# Minimum_LPC2148_2.net
KiCad netlist of a schematic drawn in EAGLE
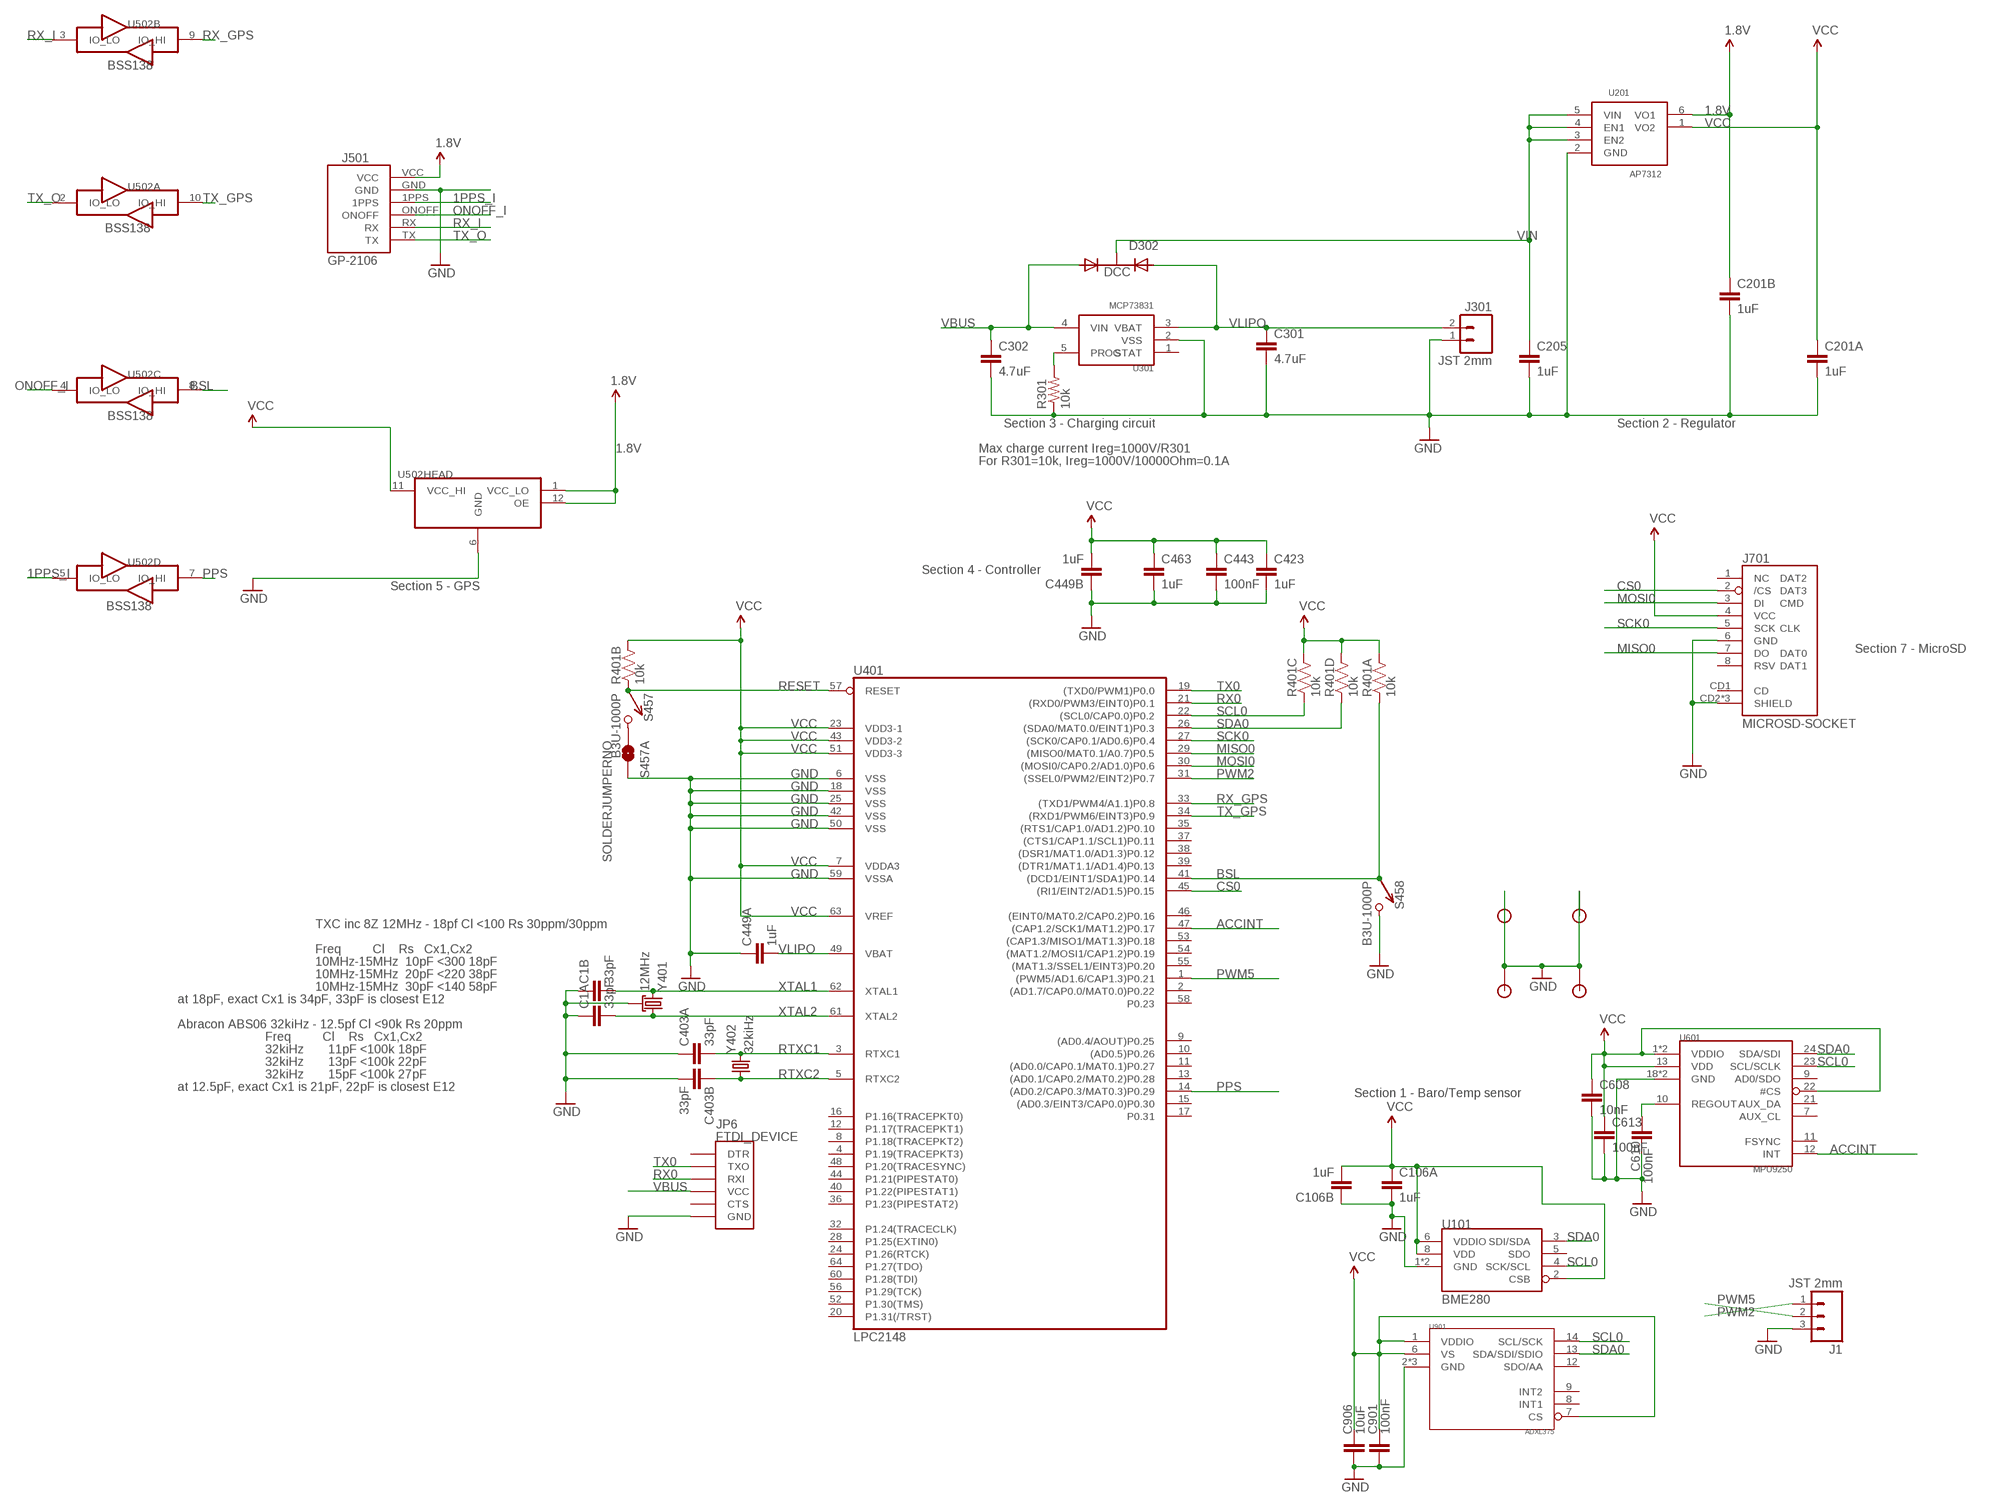
[diagram p0: schematic, sheet 1]

(export (version "E")
  (design (tool "Eeschema 10.0.6"))
  (components
    (comp (ref "C1")
      (value "33pF")
      (footprint "eagle-import:CKCM25")
      (libsource (lib "eagle-import") (part "CKCM25"))
    )
    (comp (ref "C106")
      (value "1uF")
      (footprint "eagle-import:CKCM25")
      (libsource (lib "eagle-import") (part "CKCM25"))
    )
    (comp (ref "C201")
      (value "1uF")
      (footprint "eagle-import:CKCM25")
      (libsource (lib "eagle-import") (part "CKCM25"))
    )
    (comp (ref "C205")
      (value "1uF")
      (footprint "eagle-import:0402-CAP")
      (libsource (lib "eagle-import") (part "CAP0402-CAP"))
    )
    (comp (ref "C301")
      (value "4.7uF")
      (footprint "eagle-import:0402-CAP")
      (libsource (lib "eagle-import") (part "CAP0402-CAP"))
    )
    (comp (ref "C302")
      (value "4.7uF")
      (footprint "eagle-import:0402-CAP")
      (libsource (lib "eagle-import") (part "CAP0402-CAP"))
    )
    (comp (ref "C403")
      (value "33pF")
      (footprint "eagle-import:CKCM25")
      (libsource (lib "eagle-import") (part "CKCM25"))
    )
    (comp (ref "C423")
      (value "1uF")
      (footprint "eagle-import:0402-CAP")
      (libsource (lib "eagle-import") (part "CAP0402-CAP"))
    )
    (comp (ref "C443")
      (value "100nF")
      (footprint "eagle-import:0402-CAP")
      (libsource (lib "eagle-import") (part "CAP0402-CAP"))
    )
    (comp (ref "C449")
      (value "1uF")
      (footprint "eagle-import:CKCM25")
      (libsource (lib "eagle-import") (part "CKCM25"))
    )
    (comp (ref "C463")
      (value "1uF")
      (footprint "eagle-import:0402-CAP")
      (libsource (lib "eagle-import") (part "CAP0402-CAP"))
    )
    (comp (ref "C608")
      (value "10nF")
      (footprint "eagle-import:0402-CAP")
      (libsource (lib "eagle-import") (part "CAP0402-CAP"))
    )
    (comp (ref "C610")
      (value "100nF")
      (footprint "eagle-import:0402-CAP")
      (libsource (lib "eagle-import") (part "CAP0402-CAP"))
    )
    (comp (ref "C613")
      (value "100nF")
      (footprint "eagle-import:0402-CAP")
      (libsource (lib "eagle-import") (part "CAP0402-CAP"))
    )
    (comp (ref "C901")
      (value "100nF")
      (footprint "eagle-import:0402-CAP")
      (libsource (lib "eagle-import") (part "SparkFun-Passives_CAP0402-CAP"))
    )
    (comp (ref "C906")
      (value "10uF")
      (footprint "eagle-import:0603-CAP")
      (libsource (lib "eagle-import") (part "CAP0603-CAP"))
    )
    (comp (ref "D302")
      (value "DCC")
      (footprint "eagle-import:SOT-23-3")
      (libsource (lib "eagle-import") (part "PMEG2005CT"))
    )
    (comp (ref "J1")
      (value "JST 2mm")
      (footprint "eagle-import:1X03_NO_SILK")
      (libsource (lib "eagle-import") (part "M031X03_NO_SILK"))
    )
    (comp (ref "J301")
      (value "JST 2mm")
      (footprint "eagle-import:1X02_NO_SILK")
      (libsource (lib "eagle-import") (part "M021X02_NO_SILK"))
    )
    (comp (ref "J501")
      (value "GP-2106")
      (footprint "eagle-import:GP-2106")
      (libsource (lib "eagle-import") (part "GP-2106"))
    )
    (comp (ref "J701")
      (value "MICROSD-SOCKET")
      (footprint "eagle-import:MICROSD-SOCKET-PP")
      (libsource (lib "eagle-import") (part "MICROSD-SOCKET"))
    )
    (comp (ref "JP1")
      (value "STANDOFF")
      (footprint "eagle-import:STANDOFF")
      (libsource (lib "eagle-import") (part "STANDOFF"))
    )
    (comp (ref "JP2")
      (value "STANDOFF")
      (footprint "eagle-import:STANDOFF")
      (libsource (lib "eagle-import") (part "STANDOFF"))
    )
    (comp (ref "JP4")
      (value "STANDOFF")
      (footprint "eagle-import:STANDOFF")
      (libsource (lib "eagle-import") (part "STANDOFF"))
    )
    (comp (ref "JP5")
      (value "STANDOFF")
      (footprint "eagle-import:STANDOFF")
      (libsource (lib "eagle-import") (part "STANDOFF"))
    )
    (comp (ref "JP6")
      (value "FTDI_DEVICE")
      (footprint "eagle-import:FTDI_DEVICE_SIDE")
      (libsource (lib "eagle-import") (part "FTDI_DEVICE"))
    )
    (comp (ref "R301")
      (value "10k")
      (footprint "eagle-import:0402-RES")
      (libsource (lib "eagle-import") (part "RESISTOR0402-RES"))
    )
    (comp (ref "R401")
      (value "10k")
      (footprint "eagle-import:CRA04")
      (fields (field (name "DIGIKEY") "CRA4S810KCT-ND"))
      (libsource (lib "eagle-import") (part "RP404"))
    )
    (comp (ref "S457")
      (value "B3U-1000P")
      (footprint "eagle-import:B3U-1000P")
      (libsource (lib "eagle-import") (part "B3U-1000P"))
    )
    (comp (ref "S457A")
      (value "SOLDERJUMPERNO")
      (footprint "eagle-import:SJ_2S-NO")
      (libsource (lib "eagle-import") (part "SOLDERJUMPERNO"))
    )
    (comp (ref "S458")
      (value "B3U-1000P")
      (footprint "eagle-import:B3U-1000P")
      (libsource (lib "eagle-import") (part "B3U-1000P"))
    )
    (comp (ref "U101")
      (value "BME280")
      (footprint "eagle-import:BME280")
      (libsource (lib "eagle-import") (part "BME280"))
    )
    (comp (ref "U201")
      (value "AP7312")
      (footprint "eagle-import:SOT-23-6")
      (libsource (lib "eagle-import") (part "AP73X2"))
    )
    (comp (ref "U301")
      (value "MCP73831")
      (footprint "eagle-import:SOT-23-5")
      (libsource (lib "eagle-import") (part "MCP73831"))
    )
    (comp (ref "U401")
      (value "LPC2148")
      (footprint "eagle-import:SQFP-S-10X10-64")
      (libsource (lib "eagle-import") (part "LPC213X"))
    )
    (comp (ref "U502")
      (value "TXB0104RUT")
      (footprint "eagle-import:R-PUQFN-N12")
      (libsource (lib "eagle-import") (part "TXB0104RUT"))
    )
    (comp (ref "U601")
      (value "MPU9250")
      (footprint "eagle-import:LQFN_3MM_3MM")
      (libsource (lib "eagle-import") (part "MPU9250"))
    )
    (comp (ref "U901")
      (value "ADXL375")
      (footprint "eagle-import:ADXL375")
      (libsource (lib "eagle-import") (part "ADXL375"))
    )
    (comp (ref "Y401")
      (value "12MHz")
      (footprint "eagle-import:CRYSTAL_SMD_2MM_2_5MM")
      (libsource (lib "eagle-import") (part "CX2520"))
    )
    (comp (ref "Y402")
      (value "32kiHz")
      (footprint "eagle-import:ABS06")
      (libsource (lib "eagle-import") (part "ABS06"))
    )
  )
  (nets
    (net (code "1") (name "/1PPS_I") (class "Default")
      (node (ref "J501") (pin "1PPS") (pinfunction "1PPS_1PPS") (pintype "bidirectional"))
      (node (ref "U502") (pin "5") (pinfunction "IO_LO_5") (pintype "bidirectional"))
    )
    (net (code "2") (name "/ACCINT") (class "Default")
      (node (ref "U401") (pin "47") (pinfunction "(CAP1.2/SCK1/MAT1.2)P0.17_47") (pintype "bidirectional"))
      (node (ref "U601") (pin "12") (pinfunction "INT_12") (pintype "bidirectional"))
    )
    (net (code "3") (name "/BSL") (class "Default")
      (node (ref "R401") (pin "1") (pinfunction "1_1") (pintype "passive"))
      (node (ref "S458") (pin "P$1") (pinfunction "1_P$1") (pintype "bidirectional"))
      (node (ref "U401") (pin "41") (pinfunction "(DCD1/EINT1/SDA1)P0.14_41") (pintype "bidirectional"))
      (node (ref "U502") (pin "8") (pinfunction "IO_HI_8") (pintype "bidirectional"))
    )
    (net (code "4") (name "/CS0") (class "Default")
      (node (ref "J701") (pin "2") (pinfunction "/CS_2") (pintype "bidirectional"))
      (node (ref "U401") (pin "45") (pinfunction "(RI1/EINT2/AD1.5)P0.15_45") (pintype "bidirectional"))
    )
    (net (code "5") (name "/MISO0") (class "Default")
      (node (ref "J701") (pin "7") (pinfunction "DO_7") (pintype "bidirectional"))
      (node (ref "U401") (pin "29") (pinfunction "(MISO0/MAT0.1/A0.7)P0.5_29") (pintype "bidirectional"))
    )
    (net (code "6") (name "/MOSI0") (class "Default")
      (node (ref "J701") (pin "3") (pinfunction "DI_3") (pintype "bidirectional"))
      (node (ref "U401") (pin "30") (pinfunction "(MOSI0/CAP0.2/AD1.0)P0.6_30") (pintype "bidirectional"))
    )
    (net (code "7") (name "/ONOFF_I") (class "Default")
      (node (ref "J501") (pin "ONOFF") (pinfunction "ONOFF_ONOFF") (pintype "bidirectional"))
      (node (ref "U502") (pin "4") (pinfunction "IO_LO_4") (pintype "bidirectional"))
    )
    (net (code "8") (name "/PPS") (class "Default")
      (node (ref "U401") (pin "14") (pinfunction "(AD0.2/CAP0.3/MAT0.3)P0.29_14") (pintype "bidirectional"))
      (node (ref "U502") (pin "7") (pinfunction "IO_HI_7") (pintype "bidirectional"))
    )
    (net (code "9") (name "/PWM2") (class "Default")
      (node (ref "J1") (pin "1") (pinfunction "1_1") (pintype "passive"))
      (node (ref "U401") (pin "31") (pinfunction "(SSEL0/PWM2/EINT2)P0.7_31") (pintype "bidirectional"))
    )
    (net (code "10") (name "/PWM5") (class "Default")
      (node (ref "J1") (pin "2") (pinfunction "2_2") (pintype "passive"))
      (node (ref "U401") (pin "1") (pinfunction "(PWM5/AD1.6/CAP1.3)P0.21_1") (pintype "bidirectional"))
    )
    (net (code "11") (name "/RESET") (class "Default")
      (node (ref "R401") (pin "2") (pinfunction "1_2") (pintype "passive"))
      (node (ref "S457") (pin "P$1") (pinfunction "1_P$1") (pintype "bidirectional"))
      (node (ref "U401") (pin "57") (pinfunction "RESET_57") (pintype "input"))
    )
    (net (code "12") (name "/RTXC1") (class "Default")
      (node (ref "C403") (pin "4") (pinfunction "2_4") (pintype "passive"))
      (node (ref "U401") (pin "3") (pinfunction "RTXC1_3") (pintype "input"))
      (node (ref "Y402") (pin "2") (pinfunction "2_2") (pintype "passive"))
    )
    (net (code "13") (name "/RTXC2") (class "Default")
      (node (ref "C403") (pin "2") (pinfunction "1_2") (pintype "passive"))
      (node (ref "U401") (pin "5") (pinfunction "RTXC2_5") (pintype "output"))
      (node (ref "Y402") (pin "1") (pinfunction "1_1") (pintype "passive"))
    )
    (net (code "14") (name "/RX0") (class "Default")
      (node (ref "JP6") (pin "P$3") (pinfunction "RXI_P$3") (pintype "bidirectional"))
      (node (ref "U401") (pin "21") (pinfunction "(RXD0/PWM3/EINT0)P0.1_21") (pintype "bidirectional"))
    )
    (net (code "15") (name "/RX_GPS") (class "Default")
      (node (ref "U401") (pin "33") (pinfunction "(TXD1/PWM4/A1.1)P0.8_33") (pintype "bidirectional"))
      (node (ref "U502") (pin "9") (pinfunction "IO_HI_9") (pintype "bidirectional"))
    )
    (net (code "16") (name "/RX_I") (class "Default")
      (node (ref "J501") (pin "RX") (pinfunction "RX_RX") (pintype "bidirectional"))
      (node (ref "U502") (pin "3") (pinfunction "IO_LO_3") (pintype "bidirectional"))
    )
    (net (code "17") (name "/SCK0") (class "Default")
      (node (ref "J701") (pin "5") (pinfunction "SCK_5") (pintype "bidirectional"))
      (node (ref "U401") (pin "27") (pinfunction "(SCK0/CAP0.1/AD0.6)P0.4_27") (pintype "bidirectional"))
    )
    (net (code "18") (name "/SCL0") (class "Default")
      (node (ref "R401") (pin "3") (pinfunction "1_3") (pintype "passive"))
      (node (ref "U101") (pin "4") (pinfunction "SCK/SCL_4") (pintype "input"))
      (node (ref "U401") (pin "22") (pinfunction "(SCL0/CAP0.0)P0.2_22") (pintype "bidirectional"))
      (node (ref "U601") (pin "23") (pinfunction "SCL/SCLK_23") (pintype "bidirectional"))
      (node (ref "U901") (pin "14") (pinfunction "SCL/SCK_14") (pintype "input"))
    )
    (net (code "19") (name "/SDA0") (class "Default")
      (node (ref "R401") (pin "4") (pinfunction "1_4") (pintype "passive"))
      (node (ref "U101") (pin "3") (pinfunction "SDI/SDA_3") (pintype "bidirectional"))
      (node (ref "U401") (pin "26") (pinfunction "(SDA0/MAT0.0/EINT1)P0.3_26") (pintype "bidirectional"))
      (node (ref "U601") (pin "24") (pinfunction "SDA/SDI_24") (pintype "bidirectional"))
      (node (ref "U901") (pin "13") (pinfunction "SDA/SDI/SDIO_13") (pintype "bidirectional"))
    )
    (net (code "20") (name "/TX0") (class "Default")
      (node (ref "JP6") (pin "P$2") (pinfunction "TXO_P$2") (pintype "bidirectional"))
      (node (ref "U401") (pin "19") (pinfunction "(TXD0/PWM1)P0.0_19") (pintype "bidirectional"))
    )
    (net (code "21") (name "/TX_GPS") (class "Default")
      (node (ref "U401") (pin "34") (pinfunction "(RXD1/PWM6/EINT3)P0.9_34") (pintype "bidirectional"))
      (node (ref "U502") (pin "10") (pinfunction "IO_HI_10") (pintype "bidirectional"))
    )
    (net (code "22") (name "/TX_O") (class "Default")
      (node (ref "J501") (pin "TX") (pinfunction "TX_TX") (pintype "bidirectional"))
      (node (ref "U502") (pin "2") (pinfunction "IO_LO_2") (pintype "bidirectional"))
    )
    (net (code "23") (name "/VBUS") (class "Default")
      (node (ref "C302") (pin "1") (pinfunction "1_1") (pintype "passive"))
      (node (ref "D302") (pin "1") (pinfunction "A1_1") (pintype "passive"))
      (node (ref "JP6") (pin "P$4") (pinfunction "VCC_P$4") (pintype "bidirectional"))
      (node (ref "U301") (pin "4") (pinfunction "VIN_4") (pintype "power_in"))
    )
    (net (code "24") (name "/VIN") (class "Default")
      (node (ref "C205") (pin "1") (pinfunction "1_1") (pintype "passive"))
      (node (ref "D302") (pin "3") (pinfunction "K_3") (pintype "passive"))
      (node (ref "U201") (pin "3") (pinfunction "EN2_3") (pintype "bidirectional"))
      (node (ref "U201") (pin "4") (pinfunction "EN1_4") (pintype "bidirectional"))
      (node (ref "U201") (pin "5") (pinfunction "VIN_5") (pintype "bidirectional"))
    )
    (net (code "25") (name "/VLIPO") (class "Default")
      (node (ref "C301") (pin "1") (pinfunction "1_1") (pintype "passive"))
      (node (ref "C449") (pin "4") (pinfunction "2_4") (pintype "passive"))
      (node (ref "D302") (pin "2") (pinfunction "A2_2") (pintype "passive"))
      (node (ref "J301") (pin "2") (pinfunction "2_2") (pintype "passive"))
      (node (ref "U301") (pin "3") (pinfunction "VBAT_3") (pintype "power_in"))
      (node (ref "U401") (pin "49") (pinfunction "VBAT_49") (pintype "power_in"))
    )
    (net (code "26") (name "/XTAL1") (class "Default")
      (node (ref "C1") (pin "3") (pinfunction "2_3") (pintype "passive"))
      (node (ref "U401") (pin "62") (pinfunction "XTAL1_62") (pintype "input"))
      (node (ref "Y401") (pin "3") (pinfunction "2_3") (pintype "passive"))
    )
    (net (code "27") (name "/XTAL2") (class "Default")
      (node (ref "C1") (pin "4") (pinfunction "2_4") (pintype "passive"))
      (node (ref "U401") (pin "61") (pinfunction "XTAL2_61") (pintype "output"))
      (node (ref "Y401") (pin "1") (pinfunction "1_1") (pintype "passive"))
    )
    (net (code "28") (name "1.8V") (class "Default")
      (node (ref "C201") (pin "2") (pinfunction "1_2") (pintype "passive"))
      (node (ref "J501") (pin "VCC") (pinfunction "VCC_VCC") (pintype "bidirectional"))
      (node (ref "U201") (pin "6") (pinfunction "VO1_6") (pintype "bidirectional"))
      (node (ref "U502") (pin "1") (pinfunction "VCC_LO_1") (pintype "power_in"))
      (node (ref "U502") (pin "12") (pinfunction "OE_12") (pintype "bidirectional"))
    )
    (net (code "29") (name "GND") (class "Default")
      (node (ref "C1") (pin "1") (pinfunction "1_1") (pintype "passive"))
      (node (ref "C1") (pin "2") (pinfunction "1_2") (pintype "passive"))
      (node (ref "C106") (pin "2") (pinfunction "1_2") (pintype "passive"))
      (node (ref "C106") (pin "4") (pinfunction "2_4") (pintype "passive"))
      (node (ref "C201") (pin "3") (pinfunction "2_3") (pintype "passive"))
      (node (ref "C201") (pin "4") (pinfunction "2_4") (pintype "passive"))
      (node (ref "C205") (pin "2") (pinfunction "2_2") (pintype "passive"))
      (node (ref "C301") (pin "2") (pinfunction "2_2") (pintype "passive"))
      (node (ref "C302") (pin "2") (pinfunction "2_2") (pintype "passive"))
      (node (ref "C403") (pin "1") (pinfunction "1_1") (pintype "passive"))
      (node (ref "C403") (pin "3") (pinfunction "2_3") (pintype "passive"))
      (node (ref "C423") (pin "2") (pinfunction "2_2") (pintype "passive"))
      (node (ref "C443") (pin "2") (pinfunction "2_2") (pintype "passive"))
      (node (ref "C449") (pin "1") (pinfunction "1_1") (pintype "passive"))
      (node (ref "C449") (pin "2") (pinfunction "1_2") (pintype "passive"))
      (node (ref "C463") (pin "2") (pinfunction "2_2") (pintype "passive"))
      (node (ref "C608") (pin "2") (pinfunction "2_2") (pintype "passive"))
      (node (ref "C610") (pin "2") (pinfunction "2_2") (pintype "passive"))
      (node (ref "C613") (pin "2") (pinfunction "2_2") (pintype "passive"))
      (node (ref "C901") (pin "2") (pinfunction "2_2") (pintype "passive"))
      (node (ref "C906") (pin "2") (pinfunction "2_2") (pintype "passive"))
      (node (ref "J1") (pin "3") (pinfunction "3_3") (pintype "passive"))
      (node (ref "J301") (pin "1") (pinfunction "1_1") (pintype "passive"))
      (node (ref "J501") (pin "GND") (pinfunction "GND_GND") (pintype "bidirectional"))
      (node (ref "J701") (pin "6") (pinfunction "GND_6") (pintype "bidirectional"))
      (node (ref "J701") (pin "CD2") (pinfunction "SHIELD_CD2") (pintype "bidirectional"))
      (node (ref "J701") (pin "GND1") (pinfunction "SHIELD_GND1") (pintype "bidirectional"))
      (node (ref "J701") (pin "GND3") (pinfunction "SHIELD_GND3") (pintype "bidirectional"))
      (node (ref "JP1") (pin "P$1") (pinfunction "P$1_P$1") (pintype "bidirectional"))
      (node (ref "JP2") (pin "P$1") (pinfunction "P$1_P$1") (pintype "bidirectional"))
      (node (ref "JP4") (pin "P$1") (pinfunction "P$1_P$1") (pintype "bidirectional"))
      (node (ref "JP5") (pin "P$1") (pinfunction "P$1_P$1") (pintype "bidirectional"))
      (node (ref "JP6") (pin "P$6") (pinfunction "GND_P$6") (pintype "bidirectional"))
      (node (ref "R301") (pin "1") (pinfunction "1_1") (pintype "passive"))
      (node (ref "S457A") (pin "2") (pinfunction "2_2") (pintype "passive"))
      (node (ref "S458") (pin "P$2") (pinfunction "2_P$2") (pintype "bidirectional"))
      (node (ref "U101") (pin "1") (pinfunction "GND_1") (pintype "power_in"))
      (node (ref "U101") (pin "7") (pinfunction "GND_7") (pintype "power_in"))
      (node (ref "U201") (pin "2") (pinfunction "GND_2") (pintype "bidirectional"))
      (node (ref "U301") (pin "2") (pinfunction "VSS_2") (pintype "power_in"))
      (node (ref "U401") (pin "18") (pinfunction "VSS_18") (pintype "power_in"))
      (node (ref "U401") (pin "25") (pinfunction "VSS_25") (pintype "power_in"))
      (node (ref "U401") (pin "42") (pinfunction "VSS_42") (pintype "power_in"))
      (node (ref "U401") (pin "50") (pinfunction "VSS_50") (pintype "power_in"))
      (node (ref "U401") (pin "59") (pinfunction "VSSA_59") (pintype "power_in"))
      (node (ref "U401") (pin "6") (pinfunction "VSS_6") (pintype "power_in"))
      (node (ref "U502") (pin "6") (pinfunction "GND_6") (pintype "power_in"))
      (node (ref "U601") (pin "18") (pinfunction "GND_18") (pintype "bidirectional"))
      (node (ref "U601") (pin "20") (pinfunction "GND_20") (pintype "bidirectional"))
      (node (ref "U901") (pin "2") (pinfunction "GND_2") (pintype "power_in"))
      (node (ref "U901") (pin "4") (pinfunction "GND_4") (pintype "power_in"))
      (node (ref "U901") (pin "5") (pinfunction "GND_5") (pintype "power_in"))
      (node (ref "Y401") (pin "2") (pinfunction "GND_2") (pintype "passive"))
      (node (ref "Y401") (pin "4") (pinfunction "GND_4") (pintype "passive"))
    )
    (net (code "30") (name "Net-(S457-2)") (class "Default")
      (node (ref "S457") (pin "P$2") (pinfunction "2_P$2") (pintype "bidirectional"))
      (node (ref "S457A") (pin "1") (pinfunction "1_1") (pintype "passive"))
    )
    (net (code "31") (name "Net-(U301-PROG)") (class "Default")
      (node (ref "R301") (pin "2") (pinfunction "2_2") (pintype "passive"))
      (node (ref "U301") (pin "5") (pinfunction "PROG_5") (pintype "passive"))
    )
    (net (code "32") (name "Net-(U601-REGOUT)") (class "Default")
      (node (ref "C610") (pin "1") (pinfunction "1_1") (pintype "passive"))
      (node (ref "U601") (pin "10") (pinfunction "REGOUT_10") (pintype "bidirectional"))
    )
    (net (code "33") (name "VCC") (class "Default")
      (node (ref "C106") (pin "1") (pinfunction "1_1") (pintype "passive"))
      (node (ref "C106") (pin "3") (pinfunction "2_3") (pintype "passive"))
      (node (ref "C201") (pin "1") (pinfunction "1_1") (pintype "passive"))
      (node (ref "C423") (pin "1") (pinfunction "1_1") (pintype "passive"))
      (node (ref "C443") (pin "1") (pinfunction "1_1") (pintype "passive"))
      (node (ref "C449") (pin "3") (pinfunction "2_3") (pintype "passive"))
      (node (ref "C463") (pin "1") (pinfunction "1_1") (pintype "passive"))
      (node (ref "C608") (pin "1") (pinfunction "1_1") (pintype "passive"))
      (node (ref "C613") (pin "1") (pinfunction "1_1") (pintype "passive"))
      (node (ref "C901") (pin "1") (pinfunction "1_1") (pintype "passive"))
      (node (ref "C906") (pin "1") (pinfunction "1_1") (pintype "passive"))
      (node (ref "J701") (pin "4") (pinfunction "VCC_4") (pintype "bidirectional"))
      (node (ref "R401") (pin "5") (pinfunction "2_5") (pintype "passive"))
      (node (ref "R401") (pin "6") (pinfunction "2_6") (pintype "passive"))
      (node (ref "R401") (pin "7") (pinfunction "2_7") (pintype "passive"))
      (node (ref "R401") (pin "8") (pinfunction "2_8") (pintype "passive"))
      (node (ref "U101") (pin "2") (pinfunction "CSB_2") (pintype "input"))
      (node (ref "U101") (pin "6") (pinfunction "VDDIO_6") (pintype "power_in"))
      (node (ref "U101") (pin "8") (pinfunction "VDD_8") (pintype "power_in"))
      (node (ref "U201") (pin "1") (pinfunction "VO2_1") (pintype "bidirectional"))
      (node (ref "U401") (pin "23") (pinfunction "VDD3-1_23") (pintype "power_in"))
      (node (ref "U401") (pin "43") (pinfunction "VDD3-2_43") (pintype "power_in"))
      (node (ref "U401") (pin "51") (pinfunction "VDD3-3_51") (pintype "power_in"))
      (node (ref "U401") (pin "63") (pinfunction "VREF_63") (pintype "input"))
      (node (ref "U401") (pin "7") (pinfunction "VDDA3_7") (pintype "power_in"))
      (node (ref "U502") (pin "11") (pinfunction "VCC_HI_11") (pintype "power_in"))
      (node (ref "U601") (pin "1") (pinfunction "VDDIO_1") (pintype "bidirectional"))
      (node (ref "U601") (pin "13") (pinfunction "VDD_13") (pintype "bidirectional"))
      (node (ref "U601") (pin "22") (pinfunction "#CS_22") (pintype "bidirectional"))
      (node (ref "U601") (pin "8") (pinfunction "VDDIO_8") (pintype "bidirectional"))
      (node (ref "U901") (pin "1") (pinfunction "VDDIO_1") (pintype "power_in"))
      (node (ref "U901") (pin "6") (pinfunction "VS_6") (pintype "power_in"))
      (node (ref "U901") (pin "7") (pinfunction "CS_7") (pintype "input"))
    )
    (net (code "34") (name "unconnected-(J701-CD-PadCD1)") (class "Default")
      (node (ref "J701") (pin "CD1") (pinfunction "CD_CD1") (pintype "bidirectional"))
    )
    (net (code "35") (name "unconnected-(J701-NC-Pad1)") (class "Default")
      (node (ref "J701") (pin "1") (pinfunction "NC_1") (pintype "bidirectional"))
    )
    (net (code "36") (name "unconnected-(J701-RSV-Pad8)") (class "Default")
      (node (ref "J701") (pin "8") (pinfunction "RSV_8") (pintype "bidirectional"))
    )
    (net (code "37") (name "unconnected-(JP6-CTS-PadP$5)") (class "Default")
      (node (ref "JP6") (pin "P$5") (pinfunction "CTS_P$5") (pintype "bidirectional"))
    )
    (net (code "38") (name "unconnected-(JP6-DTR-PadP$1)") (class "Default")
      (node (ref "JP6") (pin "P$1") (pinfunction "DTR_P$1") (pintype "bidirectional"))
    )
    (net (code "39") (name "unconnected-(U101-SDO-Pad5)") (class "Default")
      (node (ref "U101") (pin "5") (pinfunction "SDO_5") (pintype "bidirectional"))
    )
    (net (code "40") (name "unconnected-(U301-STAT-Pad1)") (class "Default")
      (node (ref "U301") (pin "1") (pinfunction "STAT_1") (pintype "bidirectional"))
    )
    (net (code "41") (name "unconnected-(U401-(AD0.0{slash}CAP0.1{slash}MAT0.1)P0.27-Pad11)") (class "Default")
      (node (ref "U401") (pin "11") (pinfunction "(AD0.0/CAP0.1/MAT0.1)P0.27_11") (pintype "bidirectional"))
    )
    (net (code "42") (name "unconnected-(U401-(AD0.1{slash}CAP0.2{slash}MAT0.2)P0.28-Pad13)") (class "Default")
      (node (ref "U401") (pin "13") (pinfunction "(AD0.1/CAP0.2/MAT0.2)P0.28_13") (pintype "bidirectional"))
    )
    (net (code "43") (name "unconnected-(U401-(AD0.3{slash}EINT3{slash}CAP0.0)P0.30-Pad15)") (class "Default")
      (node (ref "U401") (pin "15") (pinfunction "(AD0.3/EINT3/CAP0.0)P0.30_15") (pintype "bidirectional"))
    )
    (net (code "44") (name "unconnected-(U401-(AD0.4{slash}AOUT)P0.25-Pad9)") (class "Default")
      (node (ref "U401") (pin "9") (pinfunction "(AD0.4/AOUT)P0.25_9") (pintype "bidirectional"))
    )
    (net (code "45") (name "unconnected-(U401-(AD0.5)P0.26-Pad10)") (class "Default")
      (node (ref "U401") (pin "10") (pinfunction "(AD0.5)P0.26_10") (pintype "bidirectional"))
    )
    (net (code "46") (name "unconnected-(U401-(AD1.7{slash}CAP0.0{slash}MAT0.0)P0.22-Pad2)") (class "Default")
      (node (ref "U401") (pin "2") (pinfunction "(AD1.7/CAP0.0/MAT0.0)P0.22_2") (pintype "bidirectional"))
    )
    (net (code "47") (name "unconnected-(U401-(CAP1.3{slash}MISO1{slash}MAT1.3)P0.18-Pad53)") (class "Default")
      (node (ref "U401") (pin "53") (pinfunction "(CAP1.3/MISO1/MAT1.3)P0.18_53") (pintype "bidirectional"))
    )
    (net (code "48") (name "unconnected-(U401-(CTS1{slash}CAP1.1{slash}SCL1)P0.11-Pad37)") (class "Default")
      (node (ref "U401") (pin "37") (pinfunction "(CTS1/CAP1.1/SCL1)P0.11_37") (pintype "bidirectional"))
    )
    (net (code "49") (name "unconnected-(U401-(DSR1{slash}MAT1.0{slash}AD1.3)P0.12-Pad38)") (class "Default")
      (node (ref "U401") (pin "38") (pinfunction "(DSR1/MAT1.0/AD1.3)P0.12_38") (pintype "bidirectional"))
    )
    (net (code "50") (name "unconnected-(U401-(DTR1{slash}MAT1.1{slash}AD1.4)P0.13-Pad39)") (class "Default")
      (node (ref "U401") (pin "39") (pinfunction "(DTR1/MAT1.1/AD1.4)P0.13_39") (pintype "bidirectional"))
    )
    (net (code "51") (name "unconnected-(U401-(EINT0{slash}MAT0.2{slash}CAP0.2)P0.16-Pad46)") (class "Default")
      (node (ref "U401") (pin "46") (pinfunction "(EINT0/MAT0.2/CAP0.2)P0.16_46") (pintype "bidirectional"))
    )
    (net (code "52") (name "unconnected-(U401-(MAT1.2{slash}MOSI1{slash}CAP1.2)P0.19-Pad54)") (class "Default")
      (node (ref "U401") (pin "54") (pinfunction "(MAT1.2/MOSI1/CAP1.2)P0.19_54") (pintype "bidirectional"))
    )
    (net (code "53") (name "unconnected-(U401-(MAT1.3{slash}SSEL1{slash}EINT3)P0.20-Pad55)") (class "Default")
      (node (ref "U401") (pin "55") (pinfunction "(MAT1.3/SSEL1/EINT3)P0.20_55") (pintype "bidirectional"))
    )
    (net (code "54") (name "unconnected-(U401-(RTS1{slash}CAP1.0{slash}AD1.2)P0.10-Pad35)") (class "Default")
      (node (ref "U401") (pin "35") (pinfunction "(RTS1/CAP1.0/AD1.2)P0.10_35") (pintype "bidirectional"))
    )
    (net (code "55") (name "unconnected-(U401-P0.23-Pad58)") (class "Default")
      (node (ref "U401") (pin "58") (pinfunction "P0.23_58") (pintype "bidirectional"))
    )
    (net (code "56") (name "unconnected-(U401-P0.31-Pad17)") (class "Default")
      (node (ref "U401") (pin "17") (pinfunction "P0.31_17") (pintype "output"))
    )
    (net (code "57") (name "unconnected-(U401-P1.16(TRACEPKT0)-Pad16)") (class "Default")
      (node (ref "U401") (pin "16") (pinfunction "P1.16(TRACEPKT0)_16") (pintype "bidirectional"))
    )
    (net (code "58") (name "unconnected-(U401-P1.17(TRACEPKT1)-Pad12)") (class "Default")
      (node (ref "U401") (pin "12") (pinfunction "P1.17(TRACEPKT1)_12") (pintype "bidirectional"))
    )
    (net (code "59") (name "unconnected-(U401-P1.18(TRACEPKT2)-Pad8)") (class "Default")
      (node (ref "U401") (pin "8") (pinfunction "P1.18(TRACEPKT2)_8") (pintype "bidirectional"))
    )
    (net (code "60") (name "unconnected-(U401-P1.19(TRACEPKT3)-Pad4)") (class "Default")
      (node (ref "U401") (pin "4") (pinfunction "P1.19(TRACEPKT3)_4") (pintype "bidirectional"))
    )
    (net (code "61") (name "unconnected-(U401-P1.20(TRACESYNC)-Pad48)") (class "Default")
      (node (ref "U401") (pin "48") (pinfunction "P1.20(TRACESYNC)_48") (pintype "bidirectional"))
    )
    (net (code "62") (name "unconnected-(U401-P1.21(PIPESTAT0)-Pad44)") (class "Default")
      (node (ref "U401") (pin "44") (pinfunction "P1.21(PIPESTAT0)_44") (pintype "bidirectional"))
    )
    (net (code "63") (name "unconnected-(U401-P1.22(PIPESTAT1)-Pad40)") (class "Default")
      (node (ref "U401") (pin "40") (pinfunction "P1.22(PIPESTAT1)_40") (pintype "bidirectional"))
    )
    (net (code "64") (name "unconnected-(U401-P1.23(PIPESTAT2)-Pad36)") (class "Default")
      (node (ref "U401") (pin "36") (pinfunction "P1.23(PIPESTAT2)_36") (pintype "bidirectional"))
    )
    (net (code "65") (name "unconnected-(U401-P1.24(TRACECLK)-Pad32)") (class "Default")
      (node (ref "U401") (pin "32") (pinfunction "P1.24(TRACECLK)_32") (pintype "bidirectional"))
    )
    (net (code "66") (name "unconnected-(U401-P1.25(EXTIN0)-Pad28)") (class "Default")
      (node (ref "U401") (pin "28") (pinfunction "P1.25(EXTIN0)_28") (pintype "bidirectional"))
    )
    (net (code "67") (name "unconnected-(U401-P1.26(RTCK)-Pad24)") (class "Default")
      (node (ref "U401") (pin "24") (pinfunction "P1.26(RTCK)_24") (pintype "bidirectional"))
    )
    (net (code "68") (name "unconnected-(U401-P1.27(TDO)-Pad64)") (class "Default")
      (node (ref "U401") (pin "64") (pinfunction "P1.27(TDO)_64") (pintype "bidirectional"))
    )
    (net (code "69") (name "unconnected-(U401-P1.28(TDI)-Pad60)") (class "Default")
      (node (ref "U401") (pin "60") (pinfunction "P1.28(TDI)_60") (pintype "bidirectional"))
    )
    (net (code "70") (name "unconnected-(U401-P1.29(TCK)-Pad56)") (class "Default")
      (node (ref "U401") (pin "56") (pinfunction "P1.29(TCK)_56") (pintype "bidirectional"))
    )
    (net (code "71") (name "unconnected-(U401-P1.30(TMS)-Pad52)") (class "Default")
      (node (ref "U401") (pin "52") (pinfunction "P1.30(TMS)_52") (pintype "bidirectional"))
    )
    (net (code "72") (name "unconnected-(U401-P1.31({slash}TRST)-Pad20)") (class "Default")
      (node (ref "U401") (pin "20") (pinfunction "P1.31(/TRST)_20") (pintype "bidirectional"))
    )
    (net (code "73") (name "unconnected-(U601-AD0{slash}SDO-Pad9)") (class "Default")
      (node (ref "U601") (pin "9") (pinfunction "AD0/SDO_9") (pintype "bidirectional"))
    )
    (net (code "74") (name "unconnected-(U601-AUX_CL-Pad7)") (class "Default")
      (node (ref "U601") (pin "7") (pinfunction "AUX_CL_7") (pintype "bidirectional"))
    )
    (net (code "75") (name "unconnected-(U601-AUX_DA-Pad21)") (class "Default")
      (node (ref "U601") (pin "21") (pinfunction "AUX_DA_21") (pintype "bidirectional"))
    )
    (net (code "76") (name "unconnected-(U601-FSYNC-Pad11)") (class "Default")
      (node (ref "U601") (pin "11") (pinfunction "FSYNC_11") (pintype "bidirectional"))
    )
    (net (code "77") (name "unconnected-(U901-INT1-Pad8)") (class "Default")
      (node (ref "U901") (pin "8") (pinfunction "INT1_8") (pintype "output"))
    )
    (net (code "78") (name "unconnected-(U901-INT2-Pad9)") (class "Default")
      (node (ref "U901") (pin "9") (pinfunction "INT2_9") (pintype "output"))
    )
    (net (code "79") (name "unconnected-(U901-SDO{slash}AA-Pad12)") (class "Default")
      (node (ref "U901") (pin "12") (pinfunction "SDO/AA_12") (pintype "bidirectional"))
    )
  )
)
